# MCU.net
KiCad netlist of a schematic drawn in Altium Designer
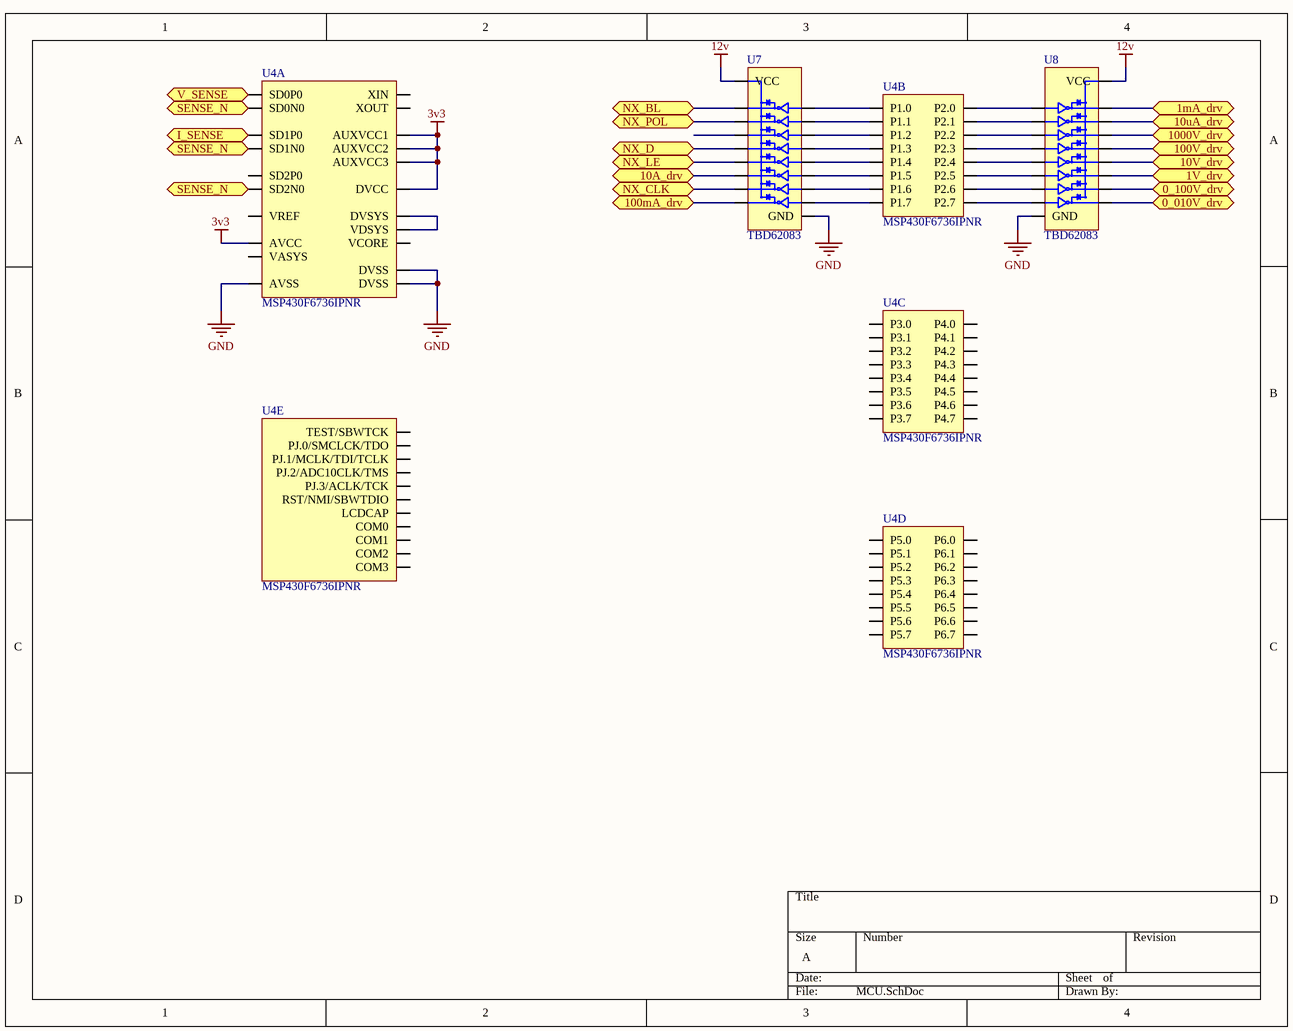
[diagram p0: MCU.SchDoc]

(export (version "E")
  (design (tool "Eeschema 10.0.6"))
  (components
    (comp (ref "U4")
      (value "MSP430F6736IPNR")
      (footprint "80-LQFP")
      (description "IC MCU 16BIT 128KB FLASH 80LQFP")
      (libsource (lib "Schlib1") (part "MSP430 F6736IPNR"))
    )
    (comp (ref "U7")
      (value "TBD62083")
      (footprint "18-SOIC")
      (description "IC LOAD SWITCH 8CH 0.5A 18SOP")
      (libsource (lib "Schlib1") (part "TBD62083"))
    )
    (comp (ref "U8")
      (value "TBD62083")
      (footprint "18-SOIC")
      (description "IC LOAD SWITCH 8CH 0.5A 18SOP")
      (libsource (lib "Schlib1") (part "TBD62083"))
    )
  )
  (nets
    (net (code "1") (name "/0_010V_drv") (class "Default")
      (node (ref "U8") (pin "11") (pinfunction "O8_11") (pintype "passive"))
    )
    (net (code "2") (name "/0_100V_drv") (class "Default")
      (node (ref "U8") (pin "12") (pinfunction "O7_12") (pintype "passive"))
    )
    (net (code "3") (name "/1V_drv") (class "Default")
      (node (ref "U8") (pin "13") (pinfunction "O6_13") (pintype "passive"))
    )
    (net (code "4") (name "/1mA_drv") (class "Default")
      (node (ref "U8") (pin "18") (pinfunction "O1_18") (pintype "passive"))
    )
    (net (code "5") (name "/10A_drv") (class "Default")
      (node (ref "U7") (pin "13") (pinfunction "O6_13") (pintype "passive"))
    )
    (net (code "6") (name "/10V_drv") (class "Default")
      (node (ref "U8") (pin "14") (pinfunction "O5_14") (pintype "passive"))
    )
    (net (code "7") (name "/10uA_drv") (class "Default")
      (node (ref "U8") (pin "17") (pinfunction "O2_17") (pintype "passive"))
    )
    (net (code "8") (name "/100V_drv") (class "Default")
      (node (ref "U8") (pin "15") (pinfunction "O4_15") (pintype "passive"))
    )
    (net (code "9") (name "/100mA_drv") (class "Default")
      (node (ref "U7") (pin "11") (pinfunction "O8_11") (pintype "passive"))
    )
    (net (code "10") (name "/1000V_drv") (class "Default")
      (node (ref "U8") (pin "16") (pinfunction "O3_16") (pintype "passive"))
    )
    (net (code "11") (name "/I_SENSE") (class "Default")
      (node (ref "U4") (pin "3") (pinfunction "SD1P0_3") (pintype "passive"))
    )
    (net (code "12") (name "/NX_BL") (class "Default")
      (node (ref "U7") (pin "18") (pinfunction "O1_18") (pintype "passive"))
    )
    (net (code "13") (name "/NX_CLK") (class "Default")
      (node (ref "U7") (pin "12") (pinfunction "O7_12") (pintype "passive"))
    )
    (net (code "14") (name "/NX_D") (class "Default")
      (node (ref "U7") (pin "15") (pinfunction "O4_15") (pintype "passive"))
    )
    (net (code "15") (name "/NX_LE") (class "Default")
      (node (ref "U7") (pin "14") (pinfunction "O5_14") (pintype "passive"))
    )
    (net (code "16") (name "/NX_POL") (class "Default")
      (node (ref "U7") (pin "17") (pinfunction "O2_17") (pintype "passive"))
    )
    (net (code "17") (name "/SENSE_N") (class "Default")
      (node (ref "U4") (pin "2") (pinfunction "SD0N0_2") (pintype "passive"))
      (node (ref "U4") (pin "4") (pinfunction "SD1N0_4") (pintype "passive"))
      (node (ref "U4") (pin "6") (pinfunction "SD2N0_6") (pintype "passive"))
    )
    (net (code "18") (name "/V_SENSE") (class "Default")
      (node (ref "U4") (pin "1") (pinfunction "SD0P0_1") (pintype "passive"))
    )
    (net (code "19") (name "3v3") (class "Default")
      (node (ref "U4") (pin "15") (pinfunction "AUXVCC2_15") (pintype "passive"))
      (node (ref "U4") (pin "16") (pinfunction "AUXVCC1_16") (pintype "passive"))
      (node (ref "U4") (pin "18") (pinfunction "DVCC_18") (pintype "passive"))
      (node (ref "U4") (pin "23") (pinfunction "AUXVCC3_23") (pintype "passive"))
      (node (ref "U4") (pin "9") (pinfunction "AVCC_9") (pintype "passive"))
    )
    (net (code "20") (name "12v") (class "Default")
      (node (ref "U7") (pin "10") (pinfunction "VCC_10") (pintype "passive"))
      (node (ref "U8") (pin "10") (pinfunction "VCC_10") (pintype "passive"))
    )
    (net (code "21") (name "GND") (class "Default")
      (node (ref "U4") (pin "19") (pinfunction "DVSS_19") (pintype "passive"))
      (node (ref "U4") (pin "60") (pinfunction "DVSS_60") (pintype "passive"))
      (node (ref "U4") (pin "8") (pinfunction "AVSS_8") (pintype "passive"))
      (node (ref "U7") (pin "9") (pinfunction "GND_9") (pintype "passive"))
      (node (ref "U8") (pin "9") (pinfunction "GND_9") (pintype "passive"))
    )
    (net (code "22") (name "Net-(U4A-DVSYS)") (class "Default")
      (node (ref "U4") (pin "17") (pinfunction "VDSYS_17") (pintype "passive"))
      (node (ref "U4") (pin "59") (pinfunction "DVSYS_59") (pintype "passive"))
    )
    (net (code "23") (name "Net-(U4B-P1.0)") (class "Default")
      (node (ref "U4") (pin "11") (pinfunction "P1.0_11") (pintype "passive"))
      (node (ref "U7") (pin "1") (pinfunction "I1_1") (pintype "passive"))
    )
    (net (code "24") (name "Net-(U4B-P1.1)") (class "Default")
      (node (ref "U4") (pin "12") (pinfunction "P1.1_12") (pintype "passive"))
      (node (ref "U7") (pin "2") (pinfunction "I2_2") (pintype "passive"))
    )
    (net (code "25") (name "Net-(U4B-P1.2)") (class "Default")
      (node (ref "U4") (pin "13") (pinfunction "P1.2_13") (pintype "passive"))
      (node (ref "U7") (pin "3") (pinfunction "I3_3") (pintype "passive"))
    )
    (net (code "26") (name "Net-(U4B-P1.3)") (class "Default")
      (node (ref "U4") (pin "14") (pinfunction "P1.3_14") (pintype "passive"))
      (node (ref "U7") (pin "4") (pinfunction "I4_4") (pintype "passive"))
    )
    (net (code "27") (name "Net-(U4B-P1.4)") (class "Default")
      (node (ref "U4") (pin "24") (pinfunction "P1.4_24") (pintype "passive"))
      (node (ref "U7") (pin "5") (pinfunction "I5_5") (pintype "passive"))
    )
    (net (code "28") (name "Net-(U4B-P1.5)") (class "Default")
      (node (ref "U4") (pin "25") (pinfunction "P1.5_25") (pintype "passive"))
      (node (ref "U7") (pin "6") (pinfunction "I6_6") (pintype "passive"))
    )
    (net (code "29") (name "Net-(U4B-P1.6)") (class "Default")
      (node (ref "U4") (pin "31") (pinfunction "P1.6_31") (pintype "passive"))
      (node (ref "U7") (pin "7") (pinfunction "I7_7") (pintype "passive"))
    )
    (net (code "30") (name "Net-(U4B-P1.7)") (class "Default")
      (node (ref "U4") (pin "32") (pinfunction "P1.7_32") (pintype "passive"))
      (node (ref "U7") (pin "8") (pinfunction "I8_8") (pintype "passive"))
    )
    (net (code "31") (name "Net-(U4B-P2.0)") (class "Default")
      (node (ref "U4") (pin "33") (pinfunction "P2.0_33") (pintype "passive"))
      (node (ref "U8") (pin "1") (pinfunction "I1_1") (pintype "passive"))
    )
    (net (code "32") (name "Net-(U4B-P2.1)") (class "Default")
      (node (ref "U4") (pin "34") (pinfunction "P2.1_34") (pintype "passive"))
      (node (ref "U8") (pin "2") (pinfunction "I2_2") (pintype "passive"))
    )
    (net (code "33") (name "Net-(U4B-P2.2)") (class "Default")
      (node (ref "U4") (pin "35") (pinfunction "P2.2_35") (pintype "passive"))
      (node (ref "U8") (pin "3") (pinfunction "I3_3") (pintype "passive"))
    )
    (net (code "34") (name "Net-(U4B-P2.3)") (class "Default")
      (node (ref "U4") (pin "36") (pinfunction "P2.3_36") (pintype "passive"))
      (node (ref "U8") (pin "4") (pinfunction "I4_4") (pintype "passive"))
    )
    (net (code "35") (name "Net-(U4B-P2.4)") (class "Default")
      (node (ref "U4") (pin "37") (pinfunction "P2.4_37") (pintype "passive"))
      (node (ref "U8") (pin "5") (pinfunction "I5_5") (pintype "passive"))
    )
    (net (code "36") (name "Net-(U4B-P2.5)") (class "Default")
      (node (ref "U4") (pin "38") (pinfunction "P2.5_38") (pintype "passive"))
      (node (ref "U8") (pin "6") (pinfunction "I6_6") (pintype "passive"))
    )
    (net (code "37") (name "Net-(U4B-P2.6)") (class "Default")
      (node (ref "U4") (pin "39") (pinfunction "P2.6_39") (pintype "passive"))
      (node (ref "U8") (pin "7") (pinfunction "I7_7") (pintype "passive"))
    )
    (net (code "38") (name "Net-(U4B-P2.7)") (class "Default")
      (node (ref "U4") (pin "40") (pinfunction "P2.7_40") (pintype "passive"))
      (node (ref "U8") (pin "8") (pinfunction "I8_8") (pintype "passive"))
    )
    (net (code "39") (name "unconnected-(U4A-SD2P0-Pad5)") (class "Default")
      (node (ref "U4") (pin "5") (pinfunction "SD2P0_5") (pintype "passive"))
    )
    (net (code "40") (name "unconnected-(U4A-VASYS-Pad10)") (class "Default")
      (node (ref "U4") (pin "10") (pinfunction "VASYS_10") (pintype "passive"))
    )
    (net (code "41") (name "unconnected-(U4A-VCORE-Pad20)") (class "Default")
      (node (ref "U4") (pin "20") (pinfunction "VCORE_20") (pintype "passive"))
    )
    (net (code "42") (name "unconnected-(U4A-VREF-Pad7)") (class "Default")
      (node (ref "U4") (pin "7") (pinfunction "VREF_7") (pintype "passive"))
    )
    (net (code "43") (name "unconnected-(U4A-XIN-Pad21)") (class "Default")
      (node (ref "U4") (pin "21") (pinfunction "XIN_21") (pintype "passive"))
    )
    (net (code "44") (name "unconnected-(U4A-XOUT-Pad22)") (class "Default")
      (node (ref "U4") (pin "22") (pinfunction "XOUT_22") (pintype "passive"))
    )
    (net (code "45") (name "unconnected-(U4C-P3.0-Pad41)") (class "Default")
      (node (ref "U4") (pin "41") (pinfunction "P3.0_41") (pintype "passive"))
    )
    (net (code "46") (name "unconnected-(U4C-P3.1-Pad42)") (class "Default")
      (node (ref "U4") (pin "42") (pinfunction "P3.1_42") (pintype "passive"))
    )
    (net (code "47") (name "unconnected-(U4C-P3.2-Pad43)") (class "Default")
      (node (ref "U4") (pin "43") (pinfunction "P3.2_43") (pintype "passive"))
    )
    (net (code "48") (name "unconnected-(U4C-P3.3-Pad44)") (class "Default")
      (node (ref "U4") (pin "44") (pinfunction "P3.3_44") (pintype "passive"))
    )
    (net (code "49") (name "unconnected-(U4C-P3.4-Pad45)") (class "Default")
      (node (ref "U4") (pin "45") (pinfunction "P3.4_45") (pintype "passive"))
    )
    (net (code "50") (name "unconnected-(U4C-P3.5-Pad46)") (class "Default")
      (node (ref "U4") (pin "46") (pinfunction "P3.5_46") (pintype "passive"))
    )
    (net (code "51") (name "unconnected-(U4C-P3.6-Pad47)") (class "Default")
      (node (ref "U4") (pin "47") (pinfunction "P3.6_47") (pintype "passive"))
    )
    (net (code "52") (name "unconnected-(U4C-P3.7-Pad48)") (class "Default")
      (node (ref "U4") (pin "48") (pinfunction "P3.7_48") (pintype "passive"))
    )
    (net (code "53") (name "unconnected-(U4C-P4.0-Pad49)") (class "Default")
      (node (ref "U4") (pin "49") (pinfunction "P4.0_49") (pintype "passive"))
    )
    (net (code "54") (name "unconnected-(U4C-P4.1-Pad50)") (class "Default")
      (node (ref "U4") (pin "50") (pinfunction "P4.1_50") (pintype "passive"))
    )
    (net (code "55") (name "unconnected-(U4C-P4.2-Pad51)") (class "Default")
      (node (ref "U4") (pin "51") (pinfunction "P4.2_51") (pintype "passive"))
    )
    (net (code "56") (name "unconnected-(U4C-P4.3-Pad52)") (class "Default")
      (node (ref "U4") (pin "52") (pinfunction "P4.3_52") (pintype "passive"))
    )
    (net (code "57") (name "unconnected-(U4C-P4.4-Pad53)") (class "Default")
      (node (ref "U4") (pin "53") (pinfunction "P4.4_53") (pintype "passive"))
    )
    (net (code "58") (name "unconnected-(U4C-P4.5-Pad54)") (class "Default")
      (node (ref "U4") (pin "54") (pinfunction "P4.5_54") (pintype "passive"))
    )
    (net (code "59") (name "unconnected-(U4C-P4.6-Pad55)") (class "Default")
      (node (ref "U4") (pin "55") (pinfunction "P4.6_55") (pintype "passive"))
    )
    (net (code "60") (name "unconnected-(U4C-P4.7-Pad56)") (class "Default")
      (node (ref "U4") (pin "56") (pinfunction "P4.7_56") (pintype "passive"))
    )
    (net (code "61") (name "unconnected-(U4D-P5.0-Pad57)") (class "Default")
      (node (ref "U4") (pin "57") (pinfunction "P5.0_57") (pintype "passive"))
    )
    (net (code "62") (name "unconnected-(U4D-P5.1-Pad58)") (class "Default")
      (node (ref "U4") (pin "58") (pinfunction "P5.1_58") (pintype "passive"))
    )
    (net (code "63") (name "unconnected-(U4D-P5.2-Pad61)") (class "Default")
      (node (ref "U4") (pin "61") (pinfunction "P5.2_61") (pintype "passive"))
    )
    (net (code "64") (name "unconnected-(U4D-P5.3-Pad62)") (class "Default")
      (node (ref "U4") (pin "62") (pinfunction "P5.3_62") (pintype "passive"))
    )
    (net (code "65") (name "unconnected-(U4D-P5.4-Pad63)") (class "Default")
      (node (ref "U4") (pin "63") (pinfunction "P5.4_63") (pintype "passive"))
    )
    (net (code "66") (name "unconnected-(U4D-P5.5-Pad64)") (class "Default")
      (node (ref "U4") (pin "64") (pinfunction "P5.5_64") (pintype "passive"))
    )
    (net (code "67") (name "unconnected-(U4D-P5.6-Pad65)") (class "Default")
      (node (ref "U4") (pin "65") (pinfunction "P5.6_65") (pintype "passive"))
    )
    (net (code "68") (name "unconnected-(U4D-P5.7-Pad66)") (class "Default")
      (node (ref "U4") (pin "66") (pinfunction "P5.7_66") (pintype "passive"))
    )
    (net (code "69") (name "unconnected-(U4D-P6.0-Pad67)") (class "Default")
      (node (ref "U4") (pin "67") (pinfunction "P6.0_67") (pintype "passive"))
    )
    (net (code "70") (name "unconnected-(U4D-P6.1-Pad68)") (class "Default")
      (node (ref "U4") (pin "68") (pinfunction "P6.1_68") (pintype "passive"))
    )
    (net (code "71") (name "unconnected-(U4D-P6.2-Pad69)") (class "Default")
      (node (ref "U4") (pin "69") (pinfunction "P6.2_69") (pintype "passive"))
    )
    (net (code "72") (name "unconnected-(U4D-P6.3-Pad70)") (class "Default")
      (node (ref "U4") (pin "70") (pinfunction "P6.3_70") (pintype "passive"))
    )
    (net (code "73") (name "unconnected-(U4D-P6.4-Pad71)") (class "Default")
      (node (ref "U4") (pin "71") (pinfunction "P6.4_71") (pintype "passive"))
    )
    (net (code "74") (name "unconnected-(U4D-P6.5-Pad72)") (class "Default")
      (node (ref "U4") (pin "72") (pinfunction "P6.5_72") (pintype "passive"))
    )
    (net (code "75") (name "unconnected-(U4D-P6.6-Pad73)") (class "Default")
      (node (ref "U4") (pin "73") (pinfunction "P6.6_73") (pintype "passive"))
    )
    (net (code "76") (name "unconnected-(U4D-P6.7-Pad74)") (class "Default")
      (node (ref "U4") (pin "74") (pinfunction "P6.7_74") (pintype "passive"))
    )
    (net (code "77") (name "unconnected-(U4E-COM0-Pad27)") (class "Default")
      (node (ref "U4") (pin "27") (pinfunction "COM0_27") (pintype "passive"))
    )
    (net (code "78") (name "unconnected-(U4E-COM1-Pad28)") (class "Default")
      (node (ref "U4") (pin "28") (pinfunction "COM1_28") (pintype "passive"))
    )
    (net (code "79") (name "unconnected-(U4E-COM2-Pad29)") (class "Default")
      (node (ref "U4") (pin "29") (pinfunction "COM2_29") (pintype "passive"))
    )
    (net (code "80") (name "unconnected-(U4E-COM3-Pad30)") (class "Default")
      (node (ref "U4") (pin "30") (pinfunction "COM3_30") (pintype "passive"))
    )
    (net (code "81") (name "unconnected-(U4E-LCDCAP-Pad26)") (class "Default")
      (node (ref "U4") (pin "26") (pinfunction "LCDCAP_26") (pintype "passive"))
    )
    (net (code "82") (name "unconnected-(U4E-PJ.0{slash}SMCLCK{slash}TDO-Pad76)") (class "Default")
      (node (ref "U4") (pin "76") (pinfunction "PJ.0/SMCLCK/TDO_76") (pintype "passive"))
    )
    (net (code "83") (name "unconnected-(U4E-PJ.1{slash}MCLK{slash}TDI{slash}TCLK-Pad77)") (class "Default")
      (node (ref "U4") (pin "77") (pinfunction "PJ.1/MCLK/TDI/TCLK_77") (pintype "passive"))
    )
    (net (code "84") (name "unconnected-(U4E-PJ.2{slash}ADC10CLK{slash}TMS-Pad78)") (class "Default")
      (node (ref "U4") (pin "78") (pinfunction "PJ.2/ADC10CLK/TMS_78") (pintype "passive"))
    )
    (net (code "85") (name "unconnected-(U4E-PJ.3{slash}ACLK{slash}TCK-Pad79)") (class "Default")
      (node (ref "U4") (pin "79") (pinfunction "PJ.3/ACLK/TCK_79") (pintype "passive"))
    )
    (net (code "86") (name "unconnected-(U4E-RST{slash}NMI{slash}SBWTDIO-Pad80)") (class "Default")
      (node (ref "U4") (pin "80") (pinfunction "RST/NMI/SBWTDIO_80") (pintype "passive"))
    )
    (net (code "87") (name "unconnected-(U4E-TEST{slash}SBWTCK-Pad75)") (class "Default")
      (node (ref "U4") (pin "75") (pinfunction "TEST/SBWTCK_75") (pintype "passive"))
    )
    (net (code "88") (name "unconnected-(U7-O3-Pad16)") (class "Default")
      (node (ref "U7") (pin "16") (pinfunction "O3_16") (pintype "passive"))
    )
  )
)
